# C210_0004_MAX_Module.net
KiCad netlist of a schematic drawn in Altium Designer
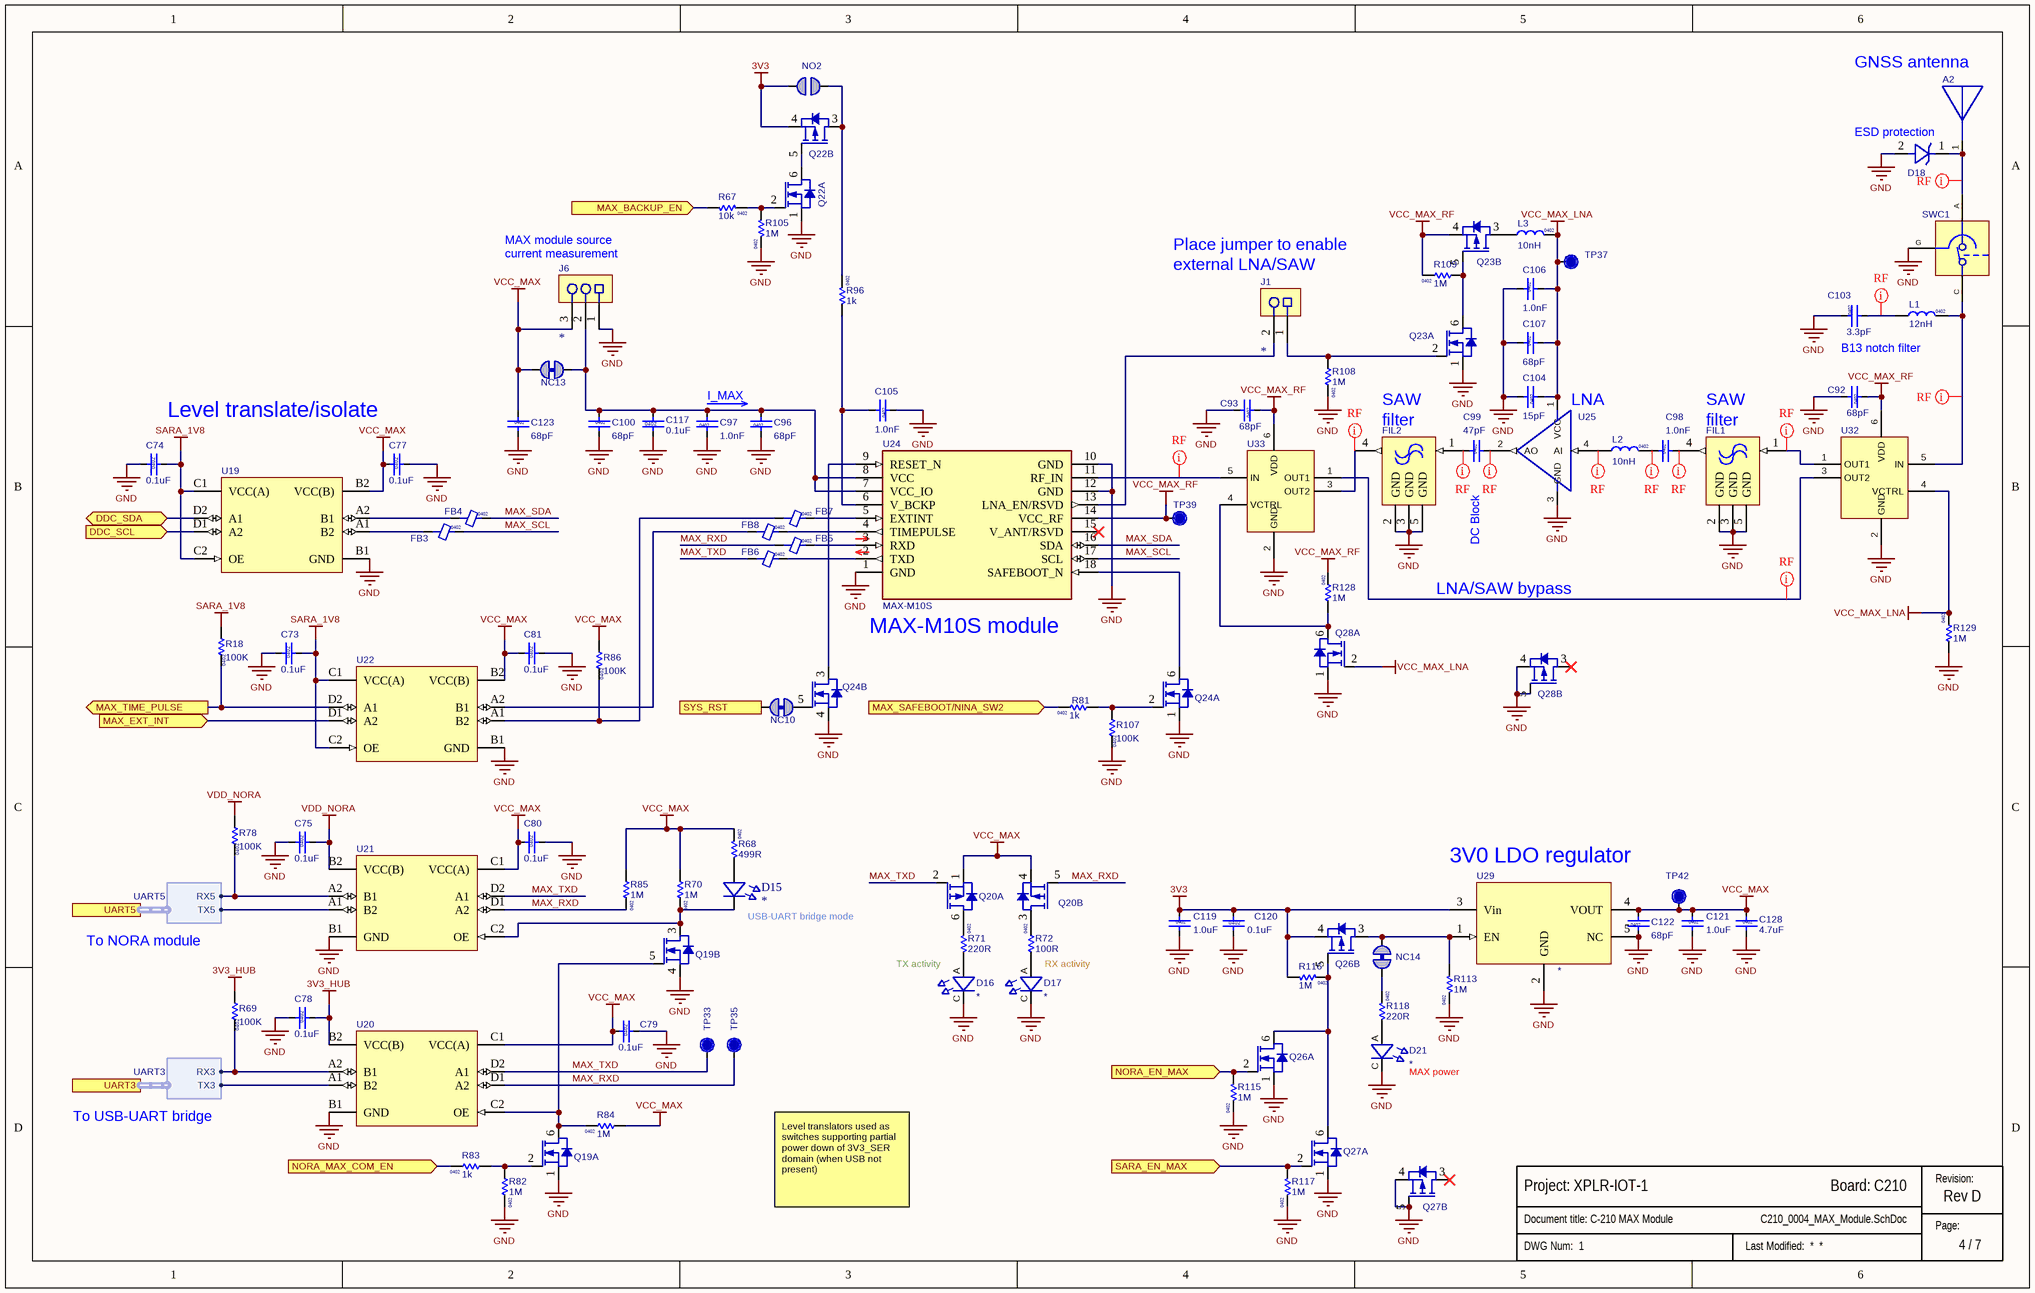
[diagram p0: C210_0004_MAX_Module.SchDoc]

(export (version "E")
  (design (tool "Eeschema 10.0.6"))
  (components
    (comp (ref "A2")
      (value "CGGP.25.4.E.02")
      (footprint "CGGP.25.4.E.02")
      (description "ANT, THROUGH-HOLE, PATCH, GNSS, BEIDOU, GLONASS, GPS, 5dBi, 25MMx35MMx4MM")
      (libsource (lib "CGGP.25.4.E.02") (part "CGGP.25.4.E.02"))
    )
    (comp (ref "C73")
      (value "0.1uF")
      (footprint "Cap 0402 HD")
      (description "Cap, Ceramic 0.1uF 10V 10% X5R 0402")
      (fields
        (field (name "SIZE") "0402")
        (field (name "PART NUMBER") "120-00016")
        (field (name "MANUFACTURER") "Murata Electronics North America")
      )
      (libsource (lib "Arena_Parts_DB_Lib") (part "Cap Chip"))
    )
    (comp (ref "C74")
      (value "0.1uF")
      (footprint "Cap 0402 HD")
      (description "Cap, Ceramic 0.1uF 10V 10% X5R 0402")
      (fields
        (field (name "SIZE") "0402")
        (field (name "PART NUMBER") "120-00016")
        (field (name "MANUFACTURER") "Murata Electronics North America")
      )
      (libsource (lib "Arena_Parts_DB_Lib") (part "Cap Chip"))
    )
    (comp (ref "C75")
      (value "0.1uF")
      (footprint "Cap 0402 HD")
      (description "Cap, Ceramic 0.1uF 10V 10% X5R 0402")
      (fields
        (field (name "SIZE") "0402")
        (field (name "PART NUMBER") "120-00016")
        (field (name "MANUFACTURER") "Murata Electronics North America")
      )
      (libsource (lib "Arena_Parts_DB_Lib") (part "Cap Chip"))
    )
    (comp (ref "C77")
      (value "0.1uF")
      (footprint "Cap 0402 HD")
      (description "Cap, Ceramic 0.1uF 10V 10% X5R 0402")
      (fields
        (field (name "SIZE") "0402")
        (field (name "PART NUMBER") "120-00016")
        (field (name "MANUFACTURER") "Murata Electronics North America")
      )
      (libsource (lib "Arena_Parts_DB_Lib") (part "Cap Chip"))
    )
    (comp (ref "C78")
      (value "0.1uF")
      (footprint "Cap 0402 HD")
      (description "Cap, Ceramic 0.1uF 10V 10% X5R 0402")
      (fields
        (field (name "SIZE") "0402")
        (field (name "PART NUMBER") "120-00016")
        (field (name "MANUFACTURER") "Murata Electronics North America")
      )
      (libsource (lib "Arena_Parts_DB_Lib") (part "Cap Chip"))
    )
    (comp (ref "C79")
      (value "0.1uF")
      (footprint "Cap 0402 HD")
      (description "Cap, Ceramic 0.1uF 10V 10% X5R 0402")
      (fields
        (field (name "SIZE") "0402")
        (field (name "PART NUMBER") "120-00016")
        (field (name "MANUFACTURER") "Murata Electronics North America")
      )
      (libsource (lib "Arena_Parts_DB_Lib") (part "Cap Chip"))
    )
    (comp (ref "C80")
      (value "0.1uF")
      (footprint "Cap 0402 HD")
      (description "Cap, Ceramic 0.1uF 10V 10% X5R 0402")
      (fields
        (field (name "SIZE") "0402")
        (field (name "PART NUMBER") "120-00016")
        (field (name "MANUFACTURER") "Murata Electronics North America")
      )
      (libsource (lib "Arena_Parts_DB_Lib") (part "Cap Chip"))
    )
    (comp (ref "C81")
      (value "0.1uF")
      (footprint "Cap 0402 HD")
      (description "Cap, Ceramic 0.1uF 10V 10% X5R 0402")
      (fields
        (field (name "SIZE") "0402")
        (field (name "PART NUMBER") "120-00016")
        (field (name "MANUFACTURER") "Murata Electronics North America")
      )
      (libsource (lib "Arena_Parts_DB_Lib") (part "Cap Chip"))
    )
    (comp (ref "C92")
      (value "68pF")
      (footprint "Cap 0402 HD")
      (description "Cap, Ceramic, 68pF, 50V, 1%, NP0, 0402")
      (fields
        (field (name "SIZE") "0402")
        (field (name "PART NUMBER") "120-00047")
        (field (name "TOLERANCE") "+/- 1%")
      )
      (libsource (lib "Arena_Parts_DB_Lib") (part "Cap Chip"))
    )
    (comp (ref "C93")
      (value "68pF")
      (footprint "Cap 0402 HD")
      (description "Cap, Ceramic, 68pF, 50V, 1%, NP0, 0402")
      (fields
        (field (name "SIZE") "0402")
        (field (name "PART NUMBER") "120-00047")
        (field (name "TOLERANCE") "+/- 1%")
      )
      (libsource (lib "Arena_Parts_DB_Lib") (part "Cap Chip"))
    )
    (comp (ref "C96")
      (value "68pF")
      (footprint "Cap 0402 HD")
      (description "Cap, Ceramic, 68pF, 50V, 1%, NP0, 0402")
      (fields
        (field (name "SIZE") "0402")
        (field (name "PART NUMBER") "120-00047")
        (field (name "TOLERANCE") "+/- 1%")
      )
      (libsource (lib "Arena_Parts_DB_Lib") (part "Cap Chip"))
    )
    (comp (ref "C97")
      (value "1.0nF")
      (footprint "Cap 0402 HD")
      (description "CAP CER 1.0nF 50V 10% X7R 0402")
      (fields
        (field (name "SIZE") "0402")
        (field (name "PART NUMBER") "120-00010")
        (field (name "TOLERANCE") "+/- 10%")
      )
      (libsource (lib "Arena_Parts_DB_Lib") (part "Cap Chip"))
    )
    (comp (ref "C98")
      (value "1.0nF")
      (footprint "Cap 0402 HD")
      (description "CAP CER 1.0nF 50V 10% X7R 0402")
      (fields
        (field (name "SIZE") "0402")
        (field (name "PART NUMBER") "120-00010")
        (field (name "TOLERANCE") "+/- 10%")
      )
      (libsource (lib "Arena_Parts_DB_Lib") (part "Cap Chip"))
    )
    (comp (ref "C99")
      (value "47pF")
      (footprint "Cap 0402 HD")
      (description "Cap, Ceramic 47pF 50V 5% NP0 0402")
      (fields
        (field (name "SIZE") "0402")
        (field (name "PART NUMBER") "120-00081")
        (field (name "TOLERANCE") "+/- 5%")
      )
      (libsource (lib "Arena_Parts_DB_Lib") (part "Cap Chip"))
    )
    (comp (ref "C100")
      (value "68pF")
      (footprint "Cap 0402 HD")
      (description "Cap, Ceramic, 68pF, 50V, 1%, NP0, 0402")
      (fields
        (field (name "SIZE") "0402")
        (field (name "PART NUMBER") "120-00047")
        (field (name "TOLERANCE") "+/- 1%")
      )
      (libsource (lib "Arena_Parts_DB_Lib") (part "Cap Chip"))
    )
    (comp (ref "C103")
      (value "3.3pF")
      (footprint "Cap 0402 HD")
      (description "CAP CER 3.3PF 50V +/-0.25pF NP0 0402")
      (fields
        (field (name "SIZE") "0402")
        (field (name "PART NUMBER") "120-00079")
        (field (name "TOLERANCE") "Other")
      )
      (libsource (lib "Arena_Parts_DB_Lib") (part "Cap Chip"))
    )
    (comp (ref "C104")
      (value "15pF")
      (footprint "Cap 0402 HD")
      (description "Capacitor, Ceramic, 15pF 5%, 50V, NPO, 0402")
      (fields
        (field (name "SIZE") "0402")
        (field (name "PART NUMBER") "120-00110")
        (field (name "TOLERANCE") "+/- 5%")
      )
      (libsource (lib "Arena_Parts_DB_Lib") (part "Cap Chip"))
    )
    (comp (ref "C105")
      (value "1.0nF")
      (footprint "Cap 0402 HD")
      (description "CAP CER 1.0nF 50V 10% X7R 0402")
      (fields
        (field (name "SIZE") "0402")
        (field (name "PART NUMBER") "120-00010")
        (field (name "TOLERANCE") "+/- 10%")
      )
      (libsource (lib "Arena_Parts_DB_Lib") (part "Cap Chip"))
    )
    (comp (ref "C106")
      (value "1.0nF")
      (footprint "Cap 0402 HD")
      (description "CAP CER 1.0nF 50V 10% X7R 0402")
      (fields
        (field (name "SIZE") "0402")
        (field (name "PART NUMBER") "120-00010")
        (field (name "TOLERANCE") "+/- 10%")
      )
      (libsource (lib "Arena_Parts_DB_Lib") (part "Cap Chip"))
    )
    (comp (ref "C107")
      (value "68pF")
      (footprint "Cap 0402 HD")
      (description "Cap, Ceramic, 68pF, 50V, 1%, NP0, 0402")
      (fields
        (field (name "SIZE") "0402")
        (field (name "PART NUMBER") "120-00047")
        (field (name "TOLERANCE") "+/- 1%")
      )
      (libsource (lib "Arena_Parts_DB_Lib") (part "Cap Chip"))
    )
    (comp (ref "C117")
      (value "0.1uF")
      (footprint "Cap 0402 HD")
      (description "Cap, Ceramic 0.1uF 10V 10% X5R 0402")
      (fields
        (field (name "SIZE") "0402")
        (field (name "PART NUMBER") "120-00016")
        (field (name "MANUFACTURER") "Murata Electronics North America")
      )
      (libsource (lib "Arena_Parts_DB_Lib") (part "Cap Chip"))
    )
    (comp (ref "C119")
      (value "1.0uF")
      (footprint "Cap 0402 HD")
      (description "Cap, Ceramic, 1.0uF 10V 10% X5R, 0402")
      (fields
        (field (name "SIZE") "0402")
        (field (name "PART NUMBER") "120-00017")
        (field (name "MANUFACTURER") "Murata Electronics North America")
      )
      (libsource (lib "Arena_Parts_DB_Lib") (part "Cap Chip"))
    )
    (comp (ref "C120")
      (value "0.1uF")
      (footprint "Cap 0402 HD")
      (description "Cap, Ceramic 0.1uF 10V 10% X5R 0402")
      (fields
        (field (name "SIZE") "0402")
        (field (name "PART NUMBER") "120-00016")
        (field (name "MANUFACTURER") "Murata Electronics North America")
      )
      (libsource (lib "Arena_Parts_DB_Lib") (part "Cap Chip"))
    )
    (comp (ref "C121")
      (value "1.0uF")
      (footprint "Cap 0402 HD")
      (description "Cap, Ceramic, 1.0uF 10V 10% X5R, 0402")
      (fields
        (field (name "SIZE") "0402")
        (field (name "PART NUMBER") "120-00017")
        (field (name "MANUFACTURER") "Murata Electronics North America")
      )
      (libsource (lib "Arena_Parts_DB_Lib") (part "Cap Chip"))
    )
    (comp (ref "C122")
      (value "68pF")
      (footprint "Cap 0402 HD")
      (description "Cap, Ceramic, 68pF, 50V, 1%, NP0, 0402")
      (fields
        (field (name "SIZE") "0402")
        (field (name "PART NUMBER") "120-00047")
        (field (name "TOLERANCE") "+/- 1%")
      )
      (libsource (lib "Arena_Parts_DB_Lib") (part "Cap Chip"))
    )
    (comp (ref "C123")
      (value "68pF")
      (footprint "Cap 0402 HD")
      (description "Cap, Ceramic, 68pF, 50V, 1%, NP0, 0402")
      (fields
        (field (name "SIZE") "0402")
        (field (name "PART NUMBER") "120-00047")
        (field (name "TOLERANCE") "+/- 1%")
      )
      (libsource (lib "Arena_Parts_DB_Lib") (part "Cap Chip"))
    )
    (comp (ref "C128")
      (value "4.7uF")
      (footprint "Cap 0402 HD")
      (description "Cap, Ceramic 4.7uF 10V 20% X5R 0402")
      (fields
        (field (name "SIZE") "0402")
        (field (name "PART NUMBER") "120-00020")
        (field (name "TOLERANCE") "+/- 20%")
      )
      (libsource (lib "Arena_Parts_DB_Lib") (part "Cap Chip"))
    )
    (comp (ref "D15")
      (value "115-00023")
      (footprint "LED-0603")
      (description "LED BLUE DIFFUSED 0603 SMD")
      (fields (field (name "COLOR") "*") (field (name "VOLTAGE") "None"))
      (libsource (lib "Arena_Parts_DB_Lib") (part "LED_BASE"))
    )
    (comp (ref "D16")
      (value "115-00019")
      (footprint "LTST-C190KGKT")
      (description "DIODE, LED, SMT, GREEN, CLEAR LENS, 2.0V 20mA, 0603")
      (fields (field (name "VOLTAGE") "2.0V") (field (name "COLOR") "*"))
      (libsource (lib "LTST-C190KGKT") (part "LTST-C190KGKT"))
    )
    (comp (ref "D17")
      (value "LTST-C190YKT")
      (footprint "LTST-C190YKT")
      (description "DIODE, LED, SMT, YELLOW, CLEAR LENS, 2.1V 10mA, 0603")
      (fields (field (name "VOLTAGE") "2.1V") (field (name "COLOR") "*"))
      (libsource (lib "LTST-C190YKT") (part "LTST-C190YKT"))
    )
    (comp (ref "D18")
      (value "~")
      (footprint "SOD-923_2")
      (description "Diode, TVS, SMT, ESD9101P2T5G, 3.3V, 0.5pF, SOD-923")
      (fields (field (name "VOLTAGE") "3.3V"))
      (libsource (lib "ESD9101P2T5G") (part "ESD9101P2T5G"))
    )
    (comp (ref "D21")
      (value "LTST-C190EKT")
      (footprint "LTST-C190EKT")
      (description "DIODE, LED, SMT, Red, CLEAR LENS, 2.0V 10mA, 0603")
      (fields (field (name "VOLTAGE") "2.0V") (field (name "COLOR") "*"))
      (libsource (lib "LTST-C190EKT") (part "LTST-C190EKT"))
    )
    (comp (ref "FB3")
      (value "155-00003")
      (footprint "IND 0402")
      (description "Ferrite Bead, 1k Ohm @ 100MHz, 0402")
      (fields (field (name "SIZE") "0402") (field (name "VOLTAGE") "None"))
      (libsource (lib "Arena_Parts_DB_Lib") (part "FB sm"))
    )
    (comp (ref "FB4")
      (value "155-00003")
      (footprint "IND 0402")
      (description "Ferrite Bead, 1k Ohm @ 100MHz, 0402")
      (fields (field (name "SIZE") "0402") (field (name "VOLTAGE") "None"))
      (libsource (lib "Arena_Parts_DB_Lib") (part "FB sm"))
    )
    (comp (ref "FB5")
      (value "155-00003")
      (footprint "IND 0402")
      (description "Ferrite Bead, 1k Ohm @ 100MHz, 0402")
      (fields (field (name "SIZE") "0402") (field (name "VOLTAGE") "None"))
      (libsource (lib "Arena_Parts_DB_Lib") (part "FB sm"))
    )
    (comp (ref "FB6")
      (value "155-00003")
      (footprint "IND 0402")
      (description "Ferrite Bead, 1k Ohm @ 100MHz, 0402")
      (fields (field (name "SIZE") "0402") (field (name "VOLTAGE") "None"))
      (libsource (lib "Arena_Parts_DB_Lib") (part "FB sm"))
    )
    (comp (ref "FB7")
      (value "155-00003")
      (footprint "IND 0402")
      (description "Ferrite Bead, 1k Ohm @ 100MHz, 0402")
      (fields (field (name "SIZE") "0402") (field (name "VOLTAGE") "None"))
      (libsource (lib "Arena_Parts_DB_Lib") (part "FB sm"))
    )
    (comp (ref "FB8")
      (value "155-00003")
      (footprint "IND 0402")
      (description "Ferrite Bead, 1k Ohm @ 100MHz, 0402")
      (fields (field (name "SIZE") "0402") (field (name "VOLTAGE") "None"))
      (libsource (lib "Arena_Parts_DB_Lib") (part "FB sm"))
    )
    (comp (ref "FIL1")
      (value "B39162B4353P810")
      (footprint "QCS5P")
      (description "FILTER, SMT, SAW, GNSS, 1.559-1.606GHz, LGA5")
      (libsource (lib "B39162B4353P810") (part "B39162B4353P810"))
    )
    (comp (ref "FIL2")
      (value "B39162B4353P810")
      (footprint "QCS5P")
      (description "FILTER, SMT, SAW, GNSS, 1.559-1.606GHz, LGA5")
      (libsource (lib "B39162B4353P810") (part "B39162B4353P810"))
    )
    (comp (ref "J1")
      (value "10129380-902001ALF")
      (footprint "HDR-0.1P-2Pin-1Row-SMT")
      (description "Header, 0.100\" Pitch, 2 Pin, Vertical SMT, Black")
      (fields (field (name "VOLTAGE") "None") (field (name "MANUFACTURER P/N") "*"))
      (libsource (lib "10129380-902001ALF") (part "CON-2Pin_1Row"))
    )
    (comp (ref "J6")
      (value "130-00105")
      (footprint "HDR-0.1P-3Pin-1Row-SMT")
      (description "Header, 0.100\" Pitch, 3 Pin, Vertical SMT, Black")
      (fields (field (name "MANUFACTURER P/N") "*") (field (name "VOLTAGE") "None"))
      (libsource (lib "Arena_Parts_DB_Lib") (part "CON-3Pin_1Row"))
    )
    (comp (ref "L1")
      (value "12nH")
      (footprint "IND 0402 HD")
      (description "Inductor, 12nH, 300mA, 0402")
      (fields
        (field (name "SIZE") "0402")
        (field (name "PART NUMBER") "150-00028")
        (field (name "TOLERANCE") "+/- 5%")
      )
      (libsource (lib "Arena_Parts_DB_Lib") (part "Ind sm"))
    )
    (comp (ref "L2")
      (value "10nH")
      (footprint "IND 0402")
      (description "INDUCTOR 10NH 300MA 0402")
      (fields
        (field (name "SIZE") "0402")
        (field (name "PART NUMBER") "150-00010")
        (field (name "TOLERANCE") "+/- 5%")
      )
      (libsource (lib "Arena_Parts_DB_Lib") (part "Ind sm"))
    )
    (comp (ref "L3")
      (value "10nH")
      (footprint "IND 0402")
      (description "INDUCTOR 10NH 300MA 0402")
      (fields
        (field (name "SIZE") "0402")
        (field (name "PART NUMBER") "150-00010")
        (field (name "TOLERANCE") "+/- 5%")
      )
      (libsource (lib "Arena_Parts_DB_Lib") (part "Ind sm"))
    )
    (comp (ref "NC10")
      (value "Solderbridge-ShortDNP")
      (footprint "Solderbridge-Short")
      (description "Solderbridge-Short")
      (libsource (lib "PCB_Misc") (part "Solderbridge-Short"))
    )
    (comp (ref "NC13")
      (value "Solderbridge-ShortDNP")
      (footprint "Solderbridge-Short")
      (description "Solderbridge-Short")
      (libsource (lib "PCB_Misc") (part "Solderbridge-Short"))
    )
    (comp (ref "NC14")
      (value "Solderbridge-ShortDNP")
      (footprint "Solderbridge-Short")
      (description "Solderbridge-Short")
      (libsource (lib "") (part "Solderbridge-Short_1"))
    )
    (comp (ref "NO2")
      (value "Solderbridge-OpenDNP")
      (footprint "Solderbridge-Open")
      (description "Solderbridge-Open")
      (libsource (lib "PCB_Misc") (part "Solderbridge-Open"))
    )
    (comp (ref "Q19")
      (value "140-00016")
      (footprint "SOT-563")
      (description "MOSFET 2N-CH 20V 0.8A, SOT-563")
      (fields (field (name "VOLTAGE") "20V"))
      (libsource (lib "Arena_Parts_DB_Lib") (part "MOSFET-N-Dual"))
    )
    (comp (ref "Q20")
      (value "FDY2000PZ")
      (footprint "FDY2000PZ")
      (description "MOSFET DUAL P-CH 20V SOT-563, -350mA")
      (fields (field (name "VOLTAGE") "20V"))
      (libsource (lib "FDY2000PZ") (part "MOSFET-Dual-P_Chan"))
    )
    (comp (ref "Q22")
      (value "140-00030")
      (footprint "SOT-563")
      (description "MOSFET N/P-CH 20V SOT-563, 540 mA, −430 mA")
      (fields (field (name "VOLTAGE") "20V"))
      (libsource (lib "Arena_Parts_DB_Lib") (part "MOSFET-N-P_Pair"))
    )
    (comp (ref "Q23")
      (value "140-00030")
      (footprint "SOT-563")
      (description "MOSFET N/P-CH 20V SOT-563, 540 mA, −430 mA")
      (fields (field (name "VOLTAGE") "20V"))
      (libsource (lib "Arena_Parts_DB_Lib") (part "MOSFET-N-P_Pair"))
    )
    (comp (ref "Q24")
      (value "140-00016")
      (footprint "SOT-563")
      (description "MOSFET 2N-CH 20V 0.8A, SOT-563")
      (fields (field (name "VOLTAGE") "20V"))
      (libsource (lib "Arena_Parts_DB_Lib") (part "MOSFET-N-Dual"))
    )
    (comp (ref "Q26")
      (value "140-00030")
      (footprint "SOT-563")
      (description "MOSFET N/P-CH 20V SOT-563, 540 mA, −430 mA")
      (fields (field (name "VOLTAGE") "20V"))
      (libsource (lib "Arena_Parts_DB_Lib") (part "MOSFET-N-P_Pair"))
    )
    (comp (ref "Q27")
      (value "140-00030")
      (footprint "SOT-563")
      (description "MOSFET N/P-CH 20V SOT-563, 540 mA, −430 mA")
      (fields (field (name "VOLTAGE") "20V"))
      (libsource (lib "Arena_Parts_DB_Lib") (part "MOSFET-N-P_Pair"))
    )
    (comp (ref "Q28")
      (value "140-00030")
      (footprint "SOT-563")
      (description "MOSFET N/P-CH 20V SOT-563, 540 mA, −430 mA")
      (fields (field (name "VOLTAGE") "20V"))
      (libsource (lib "Arena_Parts_DB_Lib") (part "MOSFET-N-P_Pair"))
    )
    (comp (ref "R18")
      (value "100K")
      (footprint "RES 0402 HD")
      (description "Resistor 100K ohm 1% 1/16W, 0402")
      (fields
        (field (name "SIZE") "0402")
        (field (name "PART NUMBER") "180-00093")
        (field (name "POWER") "1/16W")
      )
      (libsource (lib "Arena_Parts_DB_Lib") (part "Res sm"))
    )
    (comp (ref "R67")
      (value "10k")
      (footprint "RES 0402 HD")
      (description "Resistor 10k ohm 1% 1/16W, 0402")
      (fields
        (field (name "SIZE") "0402")
        (field (name "PART NUMBER") "180-00024")
        (field (name "POWER") "1/16W")
      )
      (libsource (lib "Arena_Parts_DB_Lib") (part "Res sm"))
    )
    (comp (ref "R68")
      (value "499R")
      (footprint "RES 0402 HD")
      (description "Resistor, 499ohm, 1%, 1/16W, 0402")
      (fields
        (field (name "SIZE") "0402")
        (field (name "PART NUMBER") "180-00031")
        (field (name "MANUFACTURER") "Rohm Semiconductor")
      )
      (libsource (lib "Arena_Parts_DB_Lib") (part "Res sm"))
    )
    (comp (ref "R69")
      (value "100K")
      (footprint "RES 0402 HD")
      (description "Resistor 100K ohm 1% 1/16W, 0402")
      (fields
        (field (name "SIZE") "0402")
        (field (name "PART NUMBER") "180-00093")
        (field (name "POWER") "1/16W")
      )
      (libsource (lib "Arena_Parts_DB_Lib") (part "Res sm"))
    )
    (comp (ref "R70")
      (value "1M")
      (footprint "RES 0402 HD")
      (description "Resistor 1M ohm 1%, 1/16W, 0402")
      (fields
        (field (name "SIZE") "0402")
        (field (name "PART NUMBER") "180-00054")
        (field (name "POWER") "1/16W")
      )
      (libsource (lib "Arena_Parts_DB_Lib") (part "Res sm"))
    )
    (comp (ref "R71")
      (value "220R")
      (footprint "RES 0402 HD")
      (description "Resistor, 220ohm, 5%, 1/16W, 0402.")
      (fields
        (field (name "SIZE") "0402")
        (field (name "PART NUMBER") "180-00098")
        (field (name "MANUFACTURER") "Panasonic Electronic Components")
      )
      (libsource (lib "Arena_Parts_DB_Lib") (part "Res sm"))
    )
    (comp (ref "R72")
      (value "100R")
      (footprint "RES 0402 HD")
      (description "Resistor, 100ohm, 1%, 1/16W, 0402.")
      (fields
        (field (name "SIZE") "0402")
        (field (name "PART NUMBER") "180-00051")
        (field (name "POWER") "1/16W")
      )
      (libsource (lib "Arena_Parts_DB_Lib") (part "Res sm"))
    )
    (comp (ref "R78")
      (value "100K")
      (footprint "RES 0402 HD")
      (description "Resistor 100K ohm 1% 1/16W, 0402")
      (fields
        (field (name "SIZE") "0402")
        (field (name "PART NUMBER") "180-00093")
        (field (name "POWER") "1/16W")
      )
      (libsource (lib "Arena_Parts_DB_Lib") (part "Res sm"))
    )
    (comp (ref "R81")
      (value "1k")
      (footprint "RES 0402 HD")
      (description "Resistor 1k ohm 1% 1/16W, 0402")
      (fields
        (field (name "SIZE") "0402")
        (field (name "PART NUMBER") "180-00021")
        (field (name "POWER") "1/16W")
      )
      (libsource (lib "Arena_Parts_DB_Lib") (part "Res sm"))
    )
    (comp (ref "R82")
      (value "1M")
      (footprint "RES 0402 HD")
      (description "Resistor 1M ohm 1%, 1/16W, 0402")
      (fields
        (field (name "SIZE") "0402")
        (field (name "PART NUMBER") "180-00054")
        (field (name "POWER") "1/16W")
      )
      (libsource (lib "Arena_Parts_DB_Lib") (part "Res sm"))
    )
    (comp (ref "R83")
      (value "1k")
      (footprint "RES 0402 HD")
      (description "Resistor 1k ohm 1% 1/16W, 0402")
      (fields
        (field (name "SIZE") "0402")
        (field (name "PART NUMBER") "180-00021")
        (field (name "POWER") "1/16W")
      )
      (libsource (lib "Arena_Parts_DB_Lib") (part "Res sm"))
    )
    (comp (ref "R84")
      (value "1M")
      (footprint "RES 0402 HD")
      (description "Resistor 1M ohm 1%, 1/16W, 0402")
      (fields
        (field (name "SIZE") "0402")
        (field (name "PART NUMBER") "180-00054")
        (field (name "POWER") "1/16W")
      )
      (libsource (lib "Arena_Parts_DB_Lib") (part "Res sm"))
    )
    (comp (ref "R85")
      (value "1M")
      (footprint "RES 0402 HD")
      (description "Resistor 1M ohm 1%, 1/16W, 0402")
      (fields
        (field (name "SIZE") "0402")
        (field (name "PART NUMBER") "180-00054")
        (field (name "POWER") "1/16W")
      )
      (libsource (lib "Arena_Parts_DB_Lib") (part "Res sm"))
    )
    (comp (ref "R86")
      (value "100K")
      (footprint "RES 0402 HD")
      (description "Resistor 100K ohm 1% 1/16W, 0402")
      (fields
        (field (name "SIZE") "0402")
        (field (name "PART NUMBER") "180-00093")
        (field (name "POWER") "1/16W")
      )
      (libsource (lib "Arena_Parts_DB_Lib") (part "Res sm"))
    )
    (comp (ref "R96")
      (value "1k")
      (footprint "RES 0402 HD")
      (description "Resistor 1k ohm 1% 1/16W, 0402")
      (fields
        (field (name "SIZE") "0402")
        (field (name "PART NUMBER") "180-00021")
        (field (name "POWER") "1/16W")
      )
      (libsource (lib "Arena_Parts_DB_Lib") (part "Res sm"))
    )
    (comp (ref "R105")
      (value "1M")
      (footprint "RES 0402 HD")
      (description "Resistor 1M ohm 1%, 1/16W, 0402")
      (fields
        (field (name "SIZE") "0402")
        (field (name "PART NUMBER") "180-00054")
        (field (name "POWER") "1/16W")
      )
      (libsource (lib "Arena_Parts_DB_Lib") (part "Res sm"))
    )
    (comp (ref "R107")
      (value "100K")
      (footprint "RES 0402 HD")
      (description "Resistor 100K ohm 1% 1/16W, 0402")
      (fields
        (field (name "SIZE") "0402")
        (field (name "PART NUMBER") "180-00093")
        (field (name "POWER") "1/16W")
      )
      (libsource (lib "Arena_Parts_DB_Lib") (part "Res sm"))
    )
    (comp (ref "R108")
      (value "1M")
      (footprint "RES 0402 HD")
      (description "Resistor 1M ohm 1%, 1/16W, 0402")
      (fields
        (field (name "SIZE") "0402")
        (field (name "PART NUMBER") "180-00054")
        (field (name "POWER") "1/16W")
      )
      (libsource (lib "Arena_Parts_DB_Lib") (part "Res sm"))
    )
    (comp (ref "R109")
      (value "1M")
      (footprint "RES 0402 HD")
      (description "Resistor 1M ohm 1%, 1/16W, 0402")
      (fields
        (field (name "SIZE") "0402")
        (field (name "PART NUMBER") "180-00054")
        (field (name "POWER") "1/16W")
      )
      (libsource (lib "Arena_Parts_DB_Lib") (part "Res sm"))
    )
    (comp (ref "R113")
      (value "1M")
      (footprint "RES 0402 HD")
      (description "Resistor 1M ohm 1%, 1/16W, 0402")
      (fields
        (field (name "SIZE") "0402")
        (field (name "PART NUMBER") "180-00054")
        (field (name "POWER") "1/16W")
      )
      (libsource (lib "Arena_Parts_DB_Lib") (part "Res sm"))
    )
    (comp (ref "R115")
      (value "1M")
      (footprint "RES 0402 HD")
      (description "Resistor 1M ohm 1%, 1/16W, 0402")
      (fields
        (field (name "SIZE") "0402")
        (field (name "PART NUMBER") "180-00054")
        (field (name "POWER") "1/16W")
      )
      (libsource (lib "Arena_Parts_DB_Lib") (part "Res sm"))
    )
    (comp (ref "R116")
      (value "1M")
      (footprint "RES 0402 HD")
      (description "Resistor 1M ohm 1%, 1/16W, 0402")
      (fields
        (field (name "SIZE") "0402")
        (field (name "PART NUMBER") "180-00054")
        (field (name "POWER") "1/16W")
      )
      (libsource (lib "Arena_Parts_DB_Lib") (part "Res sm"))
    )
    (comp (ref "R117")
      (value "1M")
      (footprint "RES 0402 HD")
      (description "Resistor 1M ohm 1%, 1/16W, 0402")
      (fields
        (field (name "SIZE") "0402")
        (field (name "PART NUMBER") "180-00054")
        (field (name "POWER") "1/16W")
      )
      (libsource (lib "Arena_Parts_DB_Lib") (part "Res sm"))
    )
    (comp (ref "R118")
      (value "220R")
      (footprint "RES 0402 HD")
      (description "Resistor, 220ohm, 5%, 1/16W, 0402.")
      (fields
        (field (name "SIZE") "0402")
        (field (name "PART NUMBER") "180-00098")
        (field (name "MANUFACTURER") "Panasonic Electronic Components")
      )
      (libsource (lib "Arena_Parts_DB_Lib") (part "Res sm"))
    )
    (comp (ref "R128")
      (value "1M")
      (footprint "RES 0402 HD")
      (description "Resistor 1M ohm 1%, 1/16W, 0402")
      (fields
        (field (name "SIZE") "0402")
        (field (name "PART NUMBER") "180-00054")
        (field (name "POWER") "1/16W")
      )
      (libsource (lib "Arena_Parts_DB_Lib") (part "Res sm"))
    )
    (comp (ref "R129")
      (value "1M")
      (footprint "RES 0402 HD")
      (description "Resistor 1M ohm 1%, 1/16W, 0402")
      (fields
        (field (name "SIZE") "0402")
        (field (name "PART NUMBER") "180-00054")
        (field (name "POWER") "1/16W")
      )
      (libsource (lib "Arena_Parts_DB_Lib") (part "Res sm"))
    )
    (comp (ref "SWC1")
      (value "MS-156C3")
      (footprint "MS-156C3")
      (description "Conn, Coax, Test, Switch, 50Ohm, SMT, 2.5mmX2.4mm")
      (fields (field (name "VOLTAGE") "None"))
      (libsource (lib "MS-156C3") (part "MS-156C3"))
    )
    (comp (ref "TP33")
      (value "TP")
      (footprint "TP12R")
      (description "Testpoint, Round 1.0mm Dia")
      (fields (field (name "PART NUMBER") "TP10R"))
      (libsource (lib "PCB_Misc") (part "TP_R"))
    )
    (comp (ref "TP35")
      (value "TP")
      (footprint "TP12R")
      (description "Testpoint, Round 1.0mm Dia")
      (fields (field (name "PART NUMBER") "TP10R"))
      (libsource (lib "PCB_Misc") (part "TP_R"))
    )
    (comp (ref "TP37")
      (value "TP")
      (footprint "TP12R")
      (description "Testpoint, Round 1.0mm Dia")
      (fields (field (name "PART NUMBER") "TP10R"))
      (libsource (lib "PCB_Misc") (part "TP_R"))
    )
    (comp (ref "TP39")
      (value "TP")
      (footprint "TP12R")
      (description "Testpoint, Round 1.0mm Dia")
      (fields (field (name "PART NUMBER") "TP10R"))
      (libsource (lib "PCB_Misc") (part "TP_R"))
    )
    (comp (ref "TP42")
      (value "TP")
      (footprint "TP12R")
      (description "Testpoint, Round 1.0mm Dia")
      (fields (field (name "PART NUMBER") "TP10R"))
      (libsource (lib "PCB_Misc") (part "TP_R"))
    )
    (comp (ref "U19")
      (value "TXS0102YZP")
      (footprint "TXS0102YZP")
      (description "IC, SMT, LEVEL TRANSLATOR, DUAL, BIDIRECTIONAL, DSBGA-8 1.9mmX0.9mm")
      (libsource (lib "") (part "TXS0102YZP_1"))
    )
    (comp (ref "U20")
      (value "TXS0102YZP")
      (footprint "TXS0102YZP")
      (description "IC, SMT, LEVEL TRANSLATOR, DUAL, BIDIRECTIONAL, DSBGA-8 1.9mmX0.9mm")
      (libsource (lib "TXS0102YZP") (part "TXS0102YZP"))
    )
    (comp (ref "U21")
      (value "TXS0102YZP")
      (footprint "TXS0102YZP")
      (description "IC, SMT, LEVEL TRANSLATOR, DUAL, BIDIRECTIONAL, DSBGA-8 1.9mmX0.9mm")
      (libsource (lib "TXS0102YZP") (part "TXS0102YZP"))
    )
    (comp (ref "U22")
      (value "TXS0102YZP")
      (footprint "TXS0102YZP")
      (description "IC, SMT, LEVEL TRANSLATOR, DUAL, BIDIRECTIONAL, DSBGA-8 1.9mmX0.9mm")
      (libsource (lib "") (part "TXS0102YZP_1"))
    )
    (comp (ref "U24")
      (value "MAX-M10S")
      (footprint "MAX-M8")
      (description "u-blox MAX GNSS module")
      (fields (field (name "MANUFACTURER") "u-blox"))
      (libsource (lib "ubloxLib") (part "MAX"))
    )
    (comp (ref "U25")
      (value "BGA123L4")
      (footprint "BGA0.4P2x2-4Pin")
      (description "LNA, SMT, GNSS, 1.1-3.6V, 1.1mA18dB, 0.75dB, BGA4")
      (fields (field (name "VOLTAGE") "1.1-3.6V"))
      (libsource (lib "BGA123L4") (part "BGA123L4"))
    )
    (comp (ref "U29")
      (value "260-00027")
      (footprint "SOT-553")
      (description "LDO, 3.0V, 200mA, SOT-5")
      (fields (field (name "MANUFACTURER P/N") "*") (field (name "VOLTAGE") "6.0V"))
      (libsource (lib "Arena_Parts_DB_Lib") (part "LDO_5Pin_TCR2LE"))
    )
    (comp (ref "U32")
      (value "SKY13585-679LF:")
      (footprint "SKY13585-679LF")
      (description "RF SWITCH, SPDT, I2C, 3-AXIS, 3-5V, 1-6GHz, SMT, DFN-6, 1mmX1mm")
      (fields (field (name "VOLTAGE") "1.9-3.6V"))
      (libsource (lib "SKY13585-679LF") (part "SKY13585-679LF{colon}"))
    )
    (comp (ref "U33")
      (value "SKY13585-679LF:")
      (footprint "SKY13585-679LF")
      (description "RF SWITCH, SPDT, I2C, 3-AXIS, 3-5V, 1-6GHz, SMT, DFN-6, 1mmX1mm")
      (fields (field (name "VOLTAGE") "1.9-3.6V"))
      (libsource (lib "") (part "SKY13585-679LF{colon}_1"))
    )
  )
  (nets
    (net (code "3") (name "/DDC_SCL") (class "Default")
      (node (ref "U19") (pin "D1") (pinfunction "A2_D1") (pintype "bidirectional"))
    )
    (net (code "4") (name "/DDC_SDA") (class "Default")
      (node (ref "U19") (pin "D2") (pinfunction "A1_D2") (pintype "bidirectional"))
    )
    (net (code "5") (name "/MAX_BACKUP_EN") (class "Default")
      (node (ref "R67") (pin "1") (pinfunction "1_1") (pintype "passive"))
    )
    (net (code "6") (name "/MAX_EXT_INT") (class "Default")
      (node (ref "U22") (pin "D1") (pinfunction "A2_D1") (pintype "bidirectional"))
    )
    (net (code "7") (name "/MAX_RXD") (class "Default")
      (node (ref "FB5") (pin "1") (pinfunction "1_1") (pintype "passive"))
      (node (ref "Q20") (pin "5") (pinfunction "G2_5") (pintype "passive"))
      (node (ref "R85") (pin "2") (pinfunction "2_2") (pintype "passive"))
      (node (ref "TP35") (pin "1") (pintype "passive"))
      (node (ref "U20") (pin "D1") (pinfunction "A2_D1") (pintype "bidirectional"))
      (node (ref "U21") (pin "D1") (pinfunction "A2_D1") (pintype "bidirectional"))
    )
    (net (code "8") (name "/MAX_SAFEBOOT{slash}NINA_SW2") (class "Default")
      (node (ref "R81") (pin "2") (pinfunction "2_2") (pintype "passive"))
    )
    (net (code "9") (name "/MAX_SCL") (class "Default")
      (node (ref "FB3") (pin "2") (pinfunction "2_2") (pintype "passive"))
      (node (ref "U24") (pin "17") (pinfunction "SCL_17") (pintype "bidirectional"))
    )
    (net (code "10") (name "/MAX_SDA") (class "Default")
      (node (ref "FB4") (pin "2") (pinfunction "2_2") (pintype "passive"))
      (node (ref "U24") (pin "16") (pinfunction "SDA_16") (pintype "bidirectional"))
    )
    (net (code "11") (name "/MAX_TIME_PULSE") (class "Default")
      (node (ref "R18") (pin "2") (pinfunction "2_2") (pintype "passive"))
      (node (ref "U22") (pin "D2") (pinfunction "A1_D2") (pintype "bidirectional"))
    )
    (net (code "12") (name "/MAX_TXD") (class "Default")
      (node (ref "FB6") (pin "1") (pinfunction "1_1") (pintype "passive"))
      (node (ref "Q20") (pin "2") (pinfunction "G1_2") (pintype "passive"))
      (node (ref "TP33") (pin "1") (pintype "passive"))
      (node (ref "U20") (pin "D2") (pinfunction "A1_D2") (pintype "bidirectional"))
      (node (ref "U21") (pin "D2") (pinfunction "A1_D2") (pintype "bidirectional"))
    )
    (net (code "13") (name "/NORA_EN_MAX") (class "Default")
      (node (ref "Q26") (pin "2") (pinfunction "G1_2") (pintype "passive"))
      (node (ref "R115") (pin "1") (pinfunction "1_1") (pintype "passive"))
    )
    (net (code "14") (name "/NORA_MAX_COM_EN") (class "Default")
      (node (ref "R83") (pin "2") (pinfunction "2_2") (pintype "passive"))
    )
    (net (code "15") (name "/RX3") (class "Default")
      (node (ref "R69") (pin "2") (pinfunction "2_2") (pintype "passive"))
      (node (ref "U20") (pin "A2") (pinfunction "B1_A2") (pintype "bidirectional"))
    )
    (net (code "16") (name "/RX5") (class "Default")
      (node (ref "R78") (pin "2") (pinfunction "2_2") (pintype "passive"))
      (node (ref "U21") (pin "A2") (pinfunction "B1_A2") (pintype "bidirectional"))
    )
    (net (code "17") (name "/SARA_EN_MAX") (class "Default")
      (node (ref "Q27") (pin "2") (pinfunction "G1_2") (pintype "passive"))
      (node (ref "R117") (pin "1") (pinfunction "1_1") (pintype "passive"))
    )
    (net (code "18") (name "/SYS_RST") (class "Default")
      (node (ref "NC10") (pin "2") (pinfunction "2_2") (pintype "passive"))
    )
    (net (code "19") (name "/TX3") (class "Default")
      (node (ref "U20") (pin "A1") (pinfunction "B2_A1") (pintype "bidirectional"))
    )
    (net (code "20") (name "/TX5") (class "Default")
      (node (ref "U21") (pin "A1") (pinfunction "B2_A1") (pintype "bidirectional"))
    )
    (net (code "23") (name "3V3") (class "Default")
      (node (ref "C119") (pin "1") (pinfunction "1_1") (pintype "passive"))
      (node (ref "C120") (pin "1") (pinfunction "1_1") (pintype "passive"))
      (node (ref "NO2") (pin "1") (pinfunction "1_1") (pintype "passive"))
      (node (ref "Q22") (pin "4") (pinfunction "S2_4") (pintype "passive"))
      (node (ref "Q26") (pin "4") (pinfunction "S2_4") (pintype "passive"))
      (node (ref "R116") (pin "1") (pinfunction "1_1") (pintype "passive"))
      (node (ref "U29") (pin "3") (pinfunction "Vin_3") (pintype "power_in"))
    )
    (net (code "24") (name "3V3_HUB") (class "Default")
      (node (ref "C78") (pin "2") (pinfunction "2_2") (pintype "passive"))
      (node (ref "R69") (pin "1") (pinfunction "1_1") (pintype "passive"))
      (node (ref "U20") (pin "B2") (pinfunction "VCC(B)_B2") (pintype "power_in"))
    )
    (net (code "25") (name "GND") (class "Default")
      (node (ref "C100") (pin "2") (pinfunction "2_2") (pintype "passive"))
      (node (ref "C103") (pin "1") (pinfunction "1_1") (pintype "passive"))
      (node (ref "C104") (pin "2") (pinfunction "2_2") (pintype "passive"))
      (node (ref "C105") (pin "1") (pinfunction "1_1") (pintype "passive"))
      (node (ref "C106") (pin "1") (pinfunction "1_1") (pintype "passive"))
      (node (ref "C107") (pin "1") (pinfunction "1_1") (pintype "passive"))
      (node (ref "C117") (pin "1") (pinfunction "1_1") (pintype "passive"))
      (node (ref "C119") (pin "2") (pinfunction "2_2") (pintype "passive"))
      (node (ref "C120") (pin "2") (pinfunction "2_2") (pintype "passive"))
      (node (ref "C121") (pin "2") (pinfunction "2_2") (pintype "passive"))
      (node (ref "C122") (pin "1") (pinfunction "1_1") (pintype "passive"))
      (node (ref "C123") (pin "2") (pinfunction "2_2") (pintype "passive"))
      (node (ref "C128") (pin "2") (pinfunction "2_2") (pintype "passive"))
      (node (ref "C73") (pin "1") (pinfunction "1_1") (pintype "passive"))
      (node (ref "C74") (pin "1") (pinfunction "1_1") (pintype "passive"))
      (node (ref "C75") (pin "1") (pinfunction "1_1") (pintype "passive"))
      (node (ref "C77") (pin "2") (pinfunction "2_2") (pintype "passive"))
      (node (ref "C78") (pin "1") (pinfunction "1_1") (pintype "passive"))
      (node (ref "C79") (pin "2") (pinfunction "2_2") (pintype "passive"))
      (node (ref "C80") (pin "2") (pinfunction "2_2") (pintype "passive"))
      (node (ref "C81") (pin "2") (pinfunction "2_2") (pintype "passive"))
      (node (ref "C92") (pin "2") (pinfunction "2_2") (pintype "passive"))
      (node (ref "C93") (pin "2") (pinfunction "2_2") (pintype "passive"))
      (node (ref "C96") (pin "1") (pinfunction "1_1") (pintype "passive"))
      (node (ref "C97") (pin "1") (pinfunction "1_1") (pintype "passive"))
      (node (ref "D16") (pin "C") (pinfunction "Cathode_C") (pintype "passive"))
      (node (ref "D17") (pin "C") (pinfunction "Cathode_C") (pintype "passive"))
      (node (ref "D18") (pin "2") (pintype "passive"))
      (node (ref "D21") (pin "C") (pinfunction "Cathode_C") (pintype "passive"))
      (node (ref "FIL1") (pin "2") (pinfunction "GND_2") (pintype "power_in"))
      (node (ref "FIL1") (pin "3") (pinfunction "GND_3") (pintype "power_in"))
      (node (ref "FIL1") (pin "5") (pinfunction "GND_5") (pintype "power_in"))
      (node (ref "FIL2") (pin "2") (pinfunction "GND_2") (pintype "power_in"))
      (node (ref "FIL2") (pin "3") (pinfunction "GND_3") (pintype "power_in"))
      (node (ref "FIL2") (pin "5") (pinfunction "GND_5") (pintype "power_in"))
      (node (ref "J6") (pin "1") (pinfunction "1_1") (pintype "passive"))
      (node (ref "Q19") (pin "1") (pinfunction "S1_1") (pintype "passive"))
      (node (ref "Q19") (pin "4") (pinfunction "S2_4") (pintype "passive"))
      (node (ref "Q22") (pin "1") (pinfunction "S1_1") (pintype "passive"))
      (node (ref "Q23") (pin "1") (pinfunction "S1_1") (pintype "passive"))
      (node (ref "Q24") (pin "1") (pinfunction "S1_1") (pintype "passive"))
      (node (ref "Q24") (pin "4") (pinfunction "S2_4") (pintype "passive"))
      (node (ref "Q26") (pin "1") (pinfunction "S1_1") (pintype "passive"))
      (node (ref "Q27") (pin "1") (pinfunction "S1_1") (pintype "passive"))
      (node (ref "Q27") (pin "4") (pinfunction "S2_4") (pintype "passive"))
      (node (ref "Q27") (pin "5") (pinfunction "G2_5") (pintype "passive"))
      (node (ref "Q28") (pin "1") (pinfunction "S1_1") (pintype "passive"))
      (node (ref "Q28") (pin "4") (pinfunction "S2_4") (pintype "passive"))
      (node (ref "Q28") (pin "5") (pinfunction "G2_5") (pintype "passive"))
      (node (ref "R105") (pin "2") (pinfunction "2_2") (pintype "passive"))
      (node (ref "R107") (pin "2") (pinfunction "2_2") (pintype "passive"))
      (node (ref "R108") (pin "2") (pinfunction "2_2") (pintype "passive"))
      (node (ref "R113") (pin "2") (pinfunction "2_2") (pintype "passive"))
      (node (ref "R115") (pin "2") (pinfunction "2_2") (pintype "passive"))
      (node (ref "R117") (pin "2") (pinfunction "2_2") (pintype "passive"))
      (node (ref "R129") (pin "1") (pinfunction "1_1") (pintype "passive"))
      (node (ref "R82") (pin "2") (pinfunction "2_2") (pintype "passive"))
      (node (ref "SWC1") (pin "G") (pinfunction "G_G") (pintype "passive"))
      (node (ref "U19") (pin "B1") (pinfunction "GND_B1") (pintype "power_in"))
      (node (ref "U20") (pin "B1") (pinfunction "GND_B1") (pintype "power_in"))
      (node (ref "U21") (pin "B1") (pinfunction "GND_B1") (pintype "power_in"))
      (node (ref "U22") (pin "B1") (pinfunction "GND_B1") (pintype "power_in"))
      (node (ref "U24") (pin "1") (pinfunction "GND_1") (pintype "power_in"))
      (node (ref "U24") (pin "10") (pinfunction "GND_10") (pintype "power_in"))
      (node (ref "U24") (pin "12") (pinfunction "GND_12") (pintype "power_in"))
      (node (ref "U25") (pin "3") (pinfunction "GND_3") (pintype "power_in"))
      (node (ref "U29") (pin "2") (pinfunction "GND_2") (pintype "power_in"))
      (node (ref "U29") (pin "5") (pinfunction "NC_5") (pintype "passive"))
      (node (ref "U32") (pin "2") (pinfunction "GND_2") (pintype "power_in"))
      (node (ref "U33") (pin "2") (pinfunction "GND_2") (pintype "power_in"))
    )
    (net (code "26") (name "Net-(A2-Pad1)") (class "Default")
      (node (ref "A2") (pin "1") (pinfunction "1_1") (pintype "passive"))
      (node (ref "D18") (pin "1") (pintype "passive"))
      (node (ref "SWC1") (pin "A") (pinfunction "A_A") (pintype "passive"))
    )
    (net (code "27") (name "Net-(C98-Pad1)") (class "Default")
      (node (ref "C98") (pin "1") (pinfunction "1_1") (pintype "passive"))
      (node (ref "L2") (pin "2") (pinfunction "2_2") (pintype "passive"))
    )
    (net (code "28") (name "Net-(C103-Pad2)") (class "Default")
      (node (ref "C103") (pin "2") (pinfunction "2_2") (pintype "passive"))
      (node (ref "L1") (pin "1") (pinfunction "1_1") (pintype "passive"))
    )
    (net (code "29") (name "Net-(D15-A)") (class "Default")
      (node (ref "D15") (pin "2") (pinfunction "A_2") (pintype "passive"))
      (node (ref "R68") (pin "1") (pinfunction "1_1") (pintype "passive"))
    )
    (net (code "30") (name "Net-(D15-C)") (class "Default")
      (node (ref "D15") (pin "1") (pinfunction "C_1") (pintype "passive"))
      (node (ref "Q19") (pin "3") (pinfunction "D2_3") (pintype "passive"))
      (node (ref "R70") (pin "2") (pinfunction "2_2") (pintype "passive"))
      (node (ref "U21") (pin "C2") (pinfunction "OE_C2") (pintype "input"))
    )
    (net (code "31") (name "Net-(D16-Anode)") (class "Default")
      (node (ref "D16") (pin "A") (pinfunction "Anode_A") (pintype "passive"))
      (node (ref "R71") (pin "1") (pinfunction "1_1") (pintype "passive"))
    )
    (net (code "32") (name "Net-(D17-Anode)") (class "Default")
      (node (ref "D17") (pin "A") (pinfunction "Anode_A") (pintype "passive"))
      (node (ref "R72") (pin "1") (pinfunction "1_1") (pintype "passive"))
    )
    (net (code "33") (name "Net-(D21-Anode)") (class "Default")
      (node (ref "D21") (pin "A") (pinfunction "Anode_A") (pintype "passive"))
      (node (ref "R118") (pin "1") (pinfunction "1_1") (pintype "passive"))
    )
    (net (code "34") (name "Net-(FIL1-Input)") (class "Default")
      (node (ref "FIL1") (pin "1") (pinfunction "Input_1") (pintype "input"))
      (node (ref "U32") (pin "1") (pinfunction "OUT1_1") (pintype "passive"))
    )
    (net (code "35") (name "Net-(FIL1-Output)") (class "Default")
      (node (ref "C98") (pin "2") (pinfunction "2_2") (pintype "passive"))
      (node (ref "FIL1") (pin "4") (pinfunction "Output_4") (pintype "output"))
    )
    (net (code "36") (name "Net-(FIL2-Input)") (class "Default")
      (node (ref "C99") (pin "1") (pinfunction "1_1") (pintype "passive"))
      (node (ref "FIL2") (pin "1") (pinfunction "Input_1") (pintype "input"))
    )
    (net (code "37") (name "Net-(FIL2-Output)") (class "Default")
      (node (ref "FIL2") (pin "4") (pinfunction "Output_4") (pintype "output"))
      (node (ref "U33") (pin "3") (pinfunction "OUT2_3") (pintype "passive"))
    )
    (net (code "38") (name "Net-(NC14-Pad2)") (class "Default")
      (node (ref "NC14") (pin "2") (pinfunction "2_2") (pintype "passive"))
      (node (ref "R118") (pin "2") (pinfunction "2_2") (pintype "passive"))
    )
    (net (code "39") (name "Net-(Q19A-D1)") (class "Default")
      (node (ref "Q19") (pin "5") (pinfunction "G2_5") (pintype "passive"))
      (node (ref "Q19") (pin "6") (pinfunction "D1_6") (pintype "passive"))
      (node (ref "R84") (pin "2") (pinfunction "2_2") (pintype "passive"))
      (node (ref "U20") (pin "C2") (pinfunction "OE_C2") (pintype "input"))
    )
    (net (code "40") (name "Net-(Q19A-G1)") (class "Default")
      (node (ref "Q19") (pin "2") (pinfunction "G1_2") (pintype "passive"))
      (node (ref "R82") (pin "1") (pinfunction "1_1") (pintype "passive"))
      (node (ref "R83") (pin "1") (pinfunction "1_1") (pintype "passive"))
    )
    (net (code "41") (name "Net-(Q20A-D1)") (class "Default")
      (node (ref "Q20") (pin "6") (pinfunction "D1_6") (pintype "passive"))
      (node (ref "R71") (pin "2") (pinfunction "2_2") (pintype "passive"))
    )
    (net (code "42") (name "Net-(Q20B-D2)") (class "Default")
      (node (ref "Q20") (pin "3") (pinfunction "D2_3") (pintype "passive"))
      (node (ref "R72") (pin "2") (pinfunction "2_2") (pintype "passive"))
    )
    (net (code "43") (name "Net-(Q22A-D1)") (class "Default")
      (node (ref "Q22") (pin "5") (pinfunction "G2_5") (pintype "passive"))
      (node (ref "Q22") (pin "6") (pinfunction "D1_6") (pintype "passive"))
    )
    (net (code "44") (name "Net-(Q22A-G1)") (class "Default")
      (node (ref "Q22") (pin "2") (pinfunction "G1_2") (pintype "passive"))
      (node (ref "R105") (pin "1") (pinfunction "1_1") (pintype "passive"))
      (node (ref "R67") (pin "2") (pinfunction "2_2") (pintype "passive"))
    )
    (net (code "45") (name "Net-(Q22B-D2)") (class "Default")
      (node (ref "NO2") (pin "2") (pinfunction "2_2") (pintype "passive"))
      (node (ref "Q22") (pin "3") (pinfunction "D2_3") (pintype "passive"))
      (node (ref "R96") (pin "2") (pinfunction "2_2") (pintype "passive"))
    )
    (net (code "46") (name "Net-(Q23A-D1)") (class "Default")
      (node (ref "Q23") (pin "5") (pinfunction "G2_5") (pintype "passive"))
      (node (ref "Q23") (pin "6") (pinfunction "D1_6") (pintype "passive"))
      (node (ref "R109") (pin "1") (pinfunction "1_1") (pintype "passive"))
    )
    (net (code "47") (name "Net-(Q23A-G1)") (class "Default")
      (node (ref "J1") (pin "1") (pinfunction "1_1") (pintype "passive"))
      (node (ref "Q23") (pin "2") (pinfunction "G1_2") (pintype "passive"))
      (node (ref "R108") (pin "1") (pinfunction "1_1") (pintype "passive"))
    )
    (net (code "48") (name "Net-(Q23B-D2)") (class "Default")
      (node (ref "L3") (pin "1") (pinfunction "1_1") (pintype "passive"))
      (node (ref "Q23") (pin "3") (pinfunction "D2_3") (pintype "passive"))
    )
    (net (code "49") (name "Net-(Q24A-D1)") (class "Default")
      (node (ref "Q24") (pin "6") (pinfunction "D1_6") (pintype "passive"))
      (node (ref "U24") (pin "18") (pinfunction "SAFEBOOT_N_18") (pintype "input"))
    )
    (net (code "50") (name "Net-(Q24A-G1)") (class "Default")
      (node (ref "Q24") (pin "2") (pinfunction "G1_2") (pintype "passive"))
      (node (ref "R107") (pin "1") (pinfunction "1_1") (pintype "passive"))
      (node (ref "R81") (pin "1") (pinfunction "1_1") (pintype "passive"))
    )
    (net (code "51") (name "Net-(Q24B-D2)") (class "Default")
      (node (ref "Q24") (pin "3") (pinfunction "D2_3") (pintype "passive"))
      (node (ref "U24") (pin "9") (pinfunction "RESET_N_9") (pintype "input"))
    )
    (net (code "52") (name "Net-(Q24B-G2)") (class "Default")
      (node (ref "NC10") (pin "1") (pinfunction "1_1") (pintype "passive"))
      (node (ref "Q24") (pin "5") (pinfunction "G2_5") (pintype "passive"))
    )
    (net (code "53") (name "Net-(Q26A-D1)") (class "Default")
      (node (ref "Q26") (pin "5") (pinfunction "G2_5") (pintype "passive"))
      (node (ref "Q26") (pin "6") (pinfunction "D1_6") (pintype "passive"))
      (node (ref "Q27") (pin "6") (pinfunction "D1_6") (pintype "passive"))
      (node (ref "R116") (pin "2") (pinfunction "2_2") (pintype "passive"))
    )
    (net (code "54") (name "Net-(Q26B-D2)") (class "Default")
      (node (ref "NC14") (pin "1") (pinfunction "1_1") (pintype "passive"))
      (node (ref "Q26") (pin "3") (pinfunction "D2_3") (pintype "passive"))
      (node (ref "R113") (pin "1") (pinfunction "1_1") (pintype "passive"))
      (node (ref "U29") (pin "1") (pinfunction "EN_1") (pintype "input"))
    )
    (net (code "55") (name "Net-(Q28A-D1)") (class "Default")
      (node (ref "Q28") (pin "6") (pinfunction "D1_6") (pintype "passive"))
      (node (ref "R128") (pin "1") (pinfunction "1_1") (pintype "passive"))
      (node (ref "U33") (pin "4") (pinfunction "VCTRL_4") (pintype "power_in"))
    )
    (net (code "56") (name "Net-(U19-B1)") (class "Default")
      (node (ref "FB4") (pin "1") (pinfunction "1_1") (pintype "passive"))
      (node (ref "U19") (pin "A2") (pinfunction "B1_A2") (pintype "bidirectional"))
    )
    (net (code "57") (name "Net-(U19-B2)") (class "Default")
      (node (ref "FB3") (pin "1") (pinfunction "1_1") (pintype "passive"))
      (node (ref "U19") (pin "A1") (pinfunction "B2_A1") (pintype "bidirectional"))
    )
    (net (code "58") (name "Net-(U22-B1)") (class "Default")
      (node (ref "FB8") (pin "1") (pinfunction "1_1") (pintype "passive"))
      (node (ref "U22") (pin "A2") (pinfunction "B1_A2") (pintype "bidirectional"))
    )
    (net (code "59") (name "Net-(U22-B2)") (class "Default")
      (node (ref "FB7") (pin "1") (pinfunction "1_1") (pintype "passive"))
      (node (ref "R86") (pin "2") (pinfunction "2_2") (pintype "passive"))
      (node (ref "U22") (pin "A1") (pinfunction "B2_A1") (pintype "bidirectional"))
    )
    (net (code "60") (name "Net-(U24-EXTINT)") (class "Default")
      (node (ref "FB7") (pin "2") (pinfunction "2_2") (pintype "passive"))
      (node (ref "U24") (pin "5") (pinfunction "EXTINT_5") (pintype "input"))
    )
    (net (code "61") (name "Net-(U24-LNA_EN{slash}RSVD)") (class "Default")
      (node (ref "J1") (pin "2") (pinfunction "2_2") (pintype "passive"))
      (node (ref "U24") (pin "13") (pinfunction "LNA_EN/RSVD_13") (pintype "output"))
    )
    (net (code "62") (name "Net-(U24-RF_IN)") (class "Default")
      (node (ref "U24") (pin "11") (pinfunction "RF_IN_11") (pintype "passive"))
      (node (ref "U33") (pin "5") (pinfunction "IN_5") (pintype "passive"))
    )
    (net (code "63") (name "Net-(U24-RXD)") (class "Default")
      (node (ref "FB5") (pin "2") (pinfunction "2_2") (pintype "passive"))
      (node (ref "U24") (pin "3") (pinfunction "RXD_3") (pintype "input"))
    )
    (net (code "64") (name "Net-(U24-TIMEPULSE)") (class "Default")
      (node (ref "FB8") (pin "2") (pinfunction "2_2") (pintype "passive"))
      (node (ref "U24") (pin "4") (pinfunction "TIMEPULSE_4") (pintype "output"))
    )
    (net (code "65") (name "Net-(U24-TXD)") (class "Default")
      (node (ref "FB6") (pin "2") (pinfunction "2_2") (pintype "passive"))
      (node (ref "U24") (pin "2") (pinfunction "TXD_2") (pintype "output"))
    )
    (net (code "66") (name "Net-(U24-VCC)") (class "Default")
      (node (ref "C100") (pin "1") (pinfunction "1_1") (pintype "passive"))
      (node (ref "C117") (pin "2") (pinfunction "2_2") (pintype "passive"))
      (node (ref "C96") (pin "2") (pinfunction "2_2") (pintype "passive"))
      (node (ref "C97") (pin "2") (pinfunction "2_2") (pintype "passive"))
      (node (ref "J6") (pin "2") (pinfunction "2_2") (pintype "passive"))
      (node (ref "NC13") (pin "1") (pinfunction "1_1") (pintype "passive"))
      (node (ref "U24") (pin "7") (pinfunction "VCC_IO_7") (pintype "power_in"))
      (node (ref "U24") (pin "8") (pinfunction "VCC_8") (pintype "power_in"))
    )
    (net (code "67") (name "Net-(U24-V_BCKP)") (class "Default")
      (node (ref "C105") (pin "2") (pinfunction "2_2") (pintype "passive"))
      (node (ref "R96") (pin "1") (pinfunction "1_1") (pintype "passive"))
      (node (ref "U24") (pin "6") (pinfunction "V_BCKP_6") (pintype "power_in"))
    )
    (net (code "68") (name "Net-(U25-AI)") (class "Default")
      (node (ref "L2") (pin "1") (pinfunction "1_1") (pintype "passive"))
      (node (ref "U25") (pin "4") (pinfunction "AI_4") (pintype "input"))
    )
    (net (code "69") (name "Net-(U25-AO)") (class "Default")
      (node (ref "C99") (pin "2") (pinfunction "2_2") (pintype "passive"))
      (node (ref "U25") (pin "2") (pinfunction "AO_2") (pintype "output"))
    )
    (net (code "70") (name "Net-(U32-IN)") (class "Default")
      (node (ref "L1") (pin "2") (pinfunction "2_2") (pintype "passive"))
      (node (ref "SWC1") (pin "C") (pinfunction "C_C") (pintype "passive"))
      (node (ref "U32") (pin "5") (pinfunction "IN_5") (pintype "passive"))
    )
    (net (code "71") (name "Net-(U32-OUT2)") (class "Default")
      (node (ref "U32") (pin "3") (pinfunction "OUT2_3") (pintype "passive"))
      (node (ref "U33") (pin "1") (pinfunction "OUT1_1") (pintype "passive"))
    )
    (net (code "72") (name "SARA_1V8") (class "Default")
      (node (ref "C73") (pin "2") (pinfunction "2_2") (pintype "passive"))
      (node (ref "C74") (pin "2") (pinfunction "2_2") (pintype "passive"))
      (node (ref "R18") (pin "1") (pinfunction "1_1") (pintype "passive"))
      (node (ref "U19") (pin "C1") (pinfunction "VCC(A)_C1") (pintype "power_in"))
      (node (ref "U19") (pin "C2") (pinfunction "OE_C2") (pintype "input"))
      (node (ref "U22") (pin "C1") (pinfunction "VCC(A)_C1") (pintype "power_in"))
      (node (ref "U22") (pin "C2") (pinfunction "OE_C2") (pintype "input"))
    )
    (net (code "73") (name "VCC_MAX") (class "Default")
      (node (ref "C121") (pin "1") (pinfunction "1_1") (pintype "passive"))
      (node (ref "C122") (pin "2") (pinfunction "2_2") (pintype "passive"))
      (node (ref "C123") (pin "1") (pinfunction "1_1") (pintype "passive"))
      (node (ref "C128") (pin "1") (pinfunction "1_1") (pintype "passive"))
      (node (ref "C77") (pin "1") (pinfunction "1_1") (pintype "passive"))
      (node (ref "C79") (pin "1") (pinfunction "1_1") (pintype "passive"))
      (node (ref "C80") (pin "1") (pinfunction "1_1") (pintype "passive"))
      (node (ref "C81") (pin "1") (pinfunction "1_1") (pintype "passive"))
      (node (ref "J6") (pin "3") (pinfunction "3_3") (pintype "passive"))
      (node (ref "NC13") (pin "2") (pinfunction "2_2") (pintype "passive"))
      (node (ref "Q20") (pin "1") (pinfunction "S1_1") (pintype "passive"))
      (node (ref "Q20") (pin "4") (pinfunction "S2_4") (pintype "passive"))
      (node (ref "R68") (pin "2") (pinfunction "2_2") (pintype "passive"))
      (node (ref "R70") (pin "1") (pinfunction "1_1") (pintype "passive"))
      (node (ref "R84") (pin "1") (pinfunction "1_1") (pintype "passive"))
      (node (ref "R85") (pin "1") (pinfunction "1_1") (pintype "passive"))
      (node (ref "R86") (pin "1") (pinfunction "1_1") (pintype "passive"))
      (node (ref "TP42") (pin "1") (pintype "passive"))
      (node (ref "U19") (pin "B2") (pinfunction "VCC(B)_B2") (pintype "power_in"))
      (node (ref "U20") (pin "C1") (pinfunction "VCC(A)_C1") (pintype "power_in"))
      (node (ref "U21") (pin "C1") (pinfunction "VCC(A)_C1") (pintype "power_in"))
      (node (ref "U22") (pin "B2") (pinfunction "VCC(B)_B2") (pintype "power_in"))
      (node (ref "U29") (pin "4") (pinfunction "VOUT_4") (pintype "power_in"))
    )
    (net (code "74") (name "VCC_MAX_LNA") (class "Default")
      (node (ref "C104") (pin "1") (pinfunction "1_1") (pintype "passive"))
      (node (ref "C106") (pin "2") (pinfunction "2_2") (pintype "passive"))
      (node (ref "C107") (pin "2") (pinfunction "2_2") (pintype "passive"))
      (node (ref "L3") (pin "2") (pinfunction "2_2") (pintype "passive"))
      (node (ref "Q28") (pin "2") (pinfunction "G1_2") (pintype "passive"))
      (node (ref "R129") (pin "2") (pinfunction "2_2") (pintype "passive"))
      (node (ref "TP37") (pin "1") (pintype "passive"))
      (node (ref "U25") (pin "1") (pinfunction "VCC_1") (pintype "power_in"))
      (node (ref "U32") (pin "4") (pinfunction "VCTRL_4") (pintype "power_in"))
    )
    (net (code "75") (name "VCC_MAX_RF") (class "Default")
      (node (ref "C92") (pin "1") (pinfunction "1_1") (pintype "passive"))
      (node (ref "C93") (pin "1") (pinfunction "1_1") (pintype "passive"))
      (node (ref "Q23") (pin "4") (pinfunction "S2_4") (pintype "passive"))
      (node (ref "R109") (pin "2") (pinfunction "2_2") (pintype "passive"))
      (node (ref "R128") (pin "2") (pinfunction "2_2") (pintype "passive"))
      (node (ref "TP39") (pin "1") (pintype "passive"))
      (node (ref "U24") (pin "14") (pinfunction "VCC_RF_14") (pintype "power_in"))
      (node (ref "U32") (pin "6") (pinfunction "VDD_6") (pintype "power_in"))
      (node (ref "U33") (pin "6") (pinfunction "VDD_6") (pintype "power_in"))
    )
    (net (code "76") (name "VDD_NORA") (class "Default")
      (node (ref "C75") (pin "2") (pinfunction "2_2") (pintype "passive"))
      (node (ref "R78") (pin "1") (pinfunction "1_1") (pintype "passive"))
      (node (ref "U21") (pin "B2") (pinfunction "VCC(B)_B2") (pintype "power_in"))
    )
    (net (code "77") (name "unconnected-(Q27B-D2-Pad3)") (class "Default")
      (node (ref "Q27") (pin "3") (pinfunction "D2_3") (pintype "passive+no_connect"))
    )
    (net (code "78") (name "unconnected-(Q28B-D2-Pad3)") (class "Default")
      (node (ref "Q28") (pin "3") (pinfunction "D2_3") (pintype "passive+no_connect"))
    )
    (net (code "79") (name "unconnected-(U24-V_ANT{slash}RSVD-Pad15)") (class "Default")
      (node (ref "U24") (pin "15") (pinfunction "V_ANT/RSVD_15") (pintype "passive+no_connect"))
    )
  )
)
